# Sheet2.net
KiCad netlist of a schematic drawn in Altium Designer
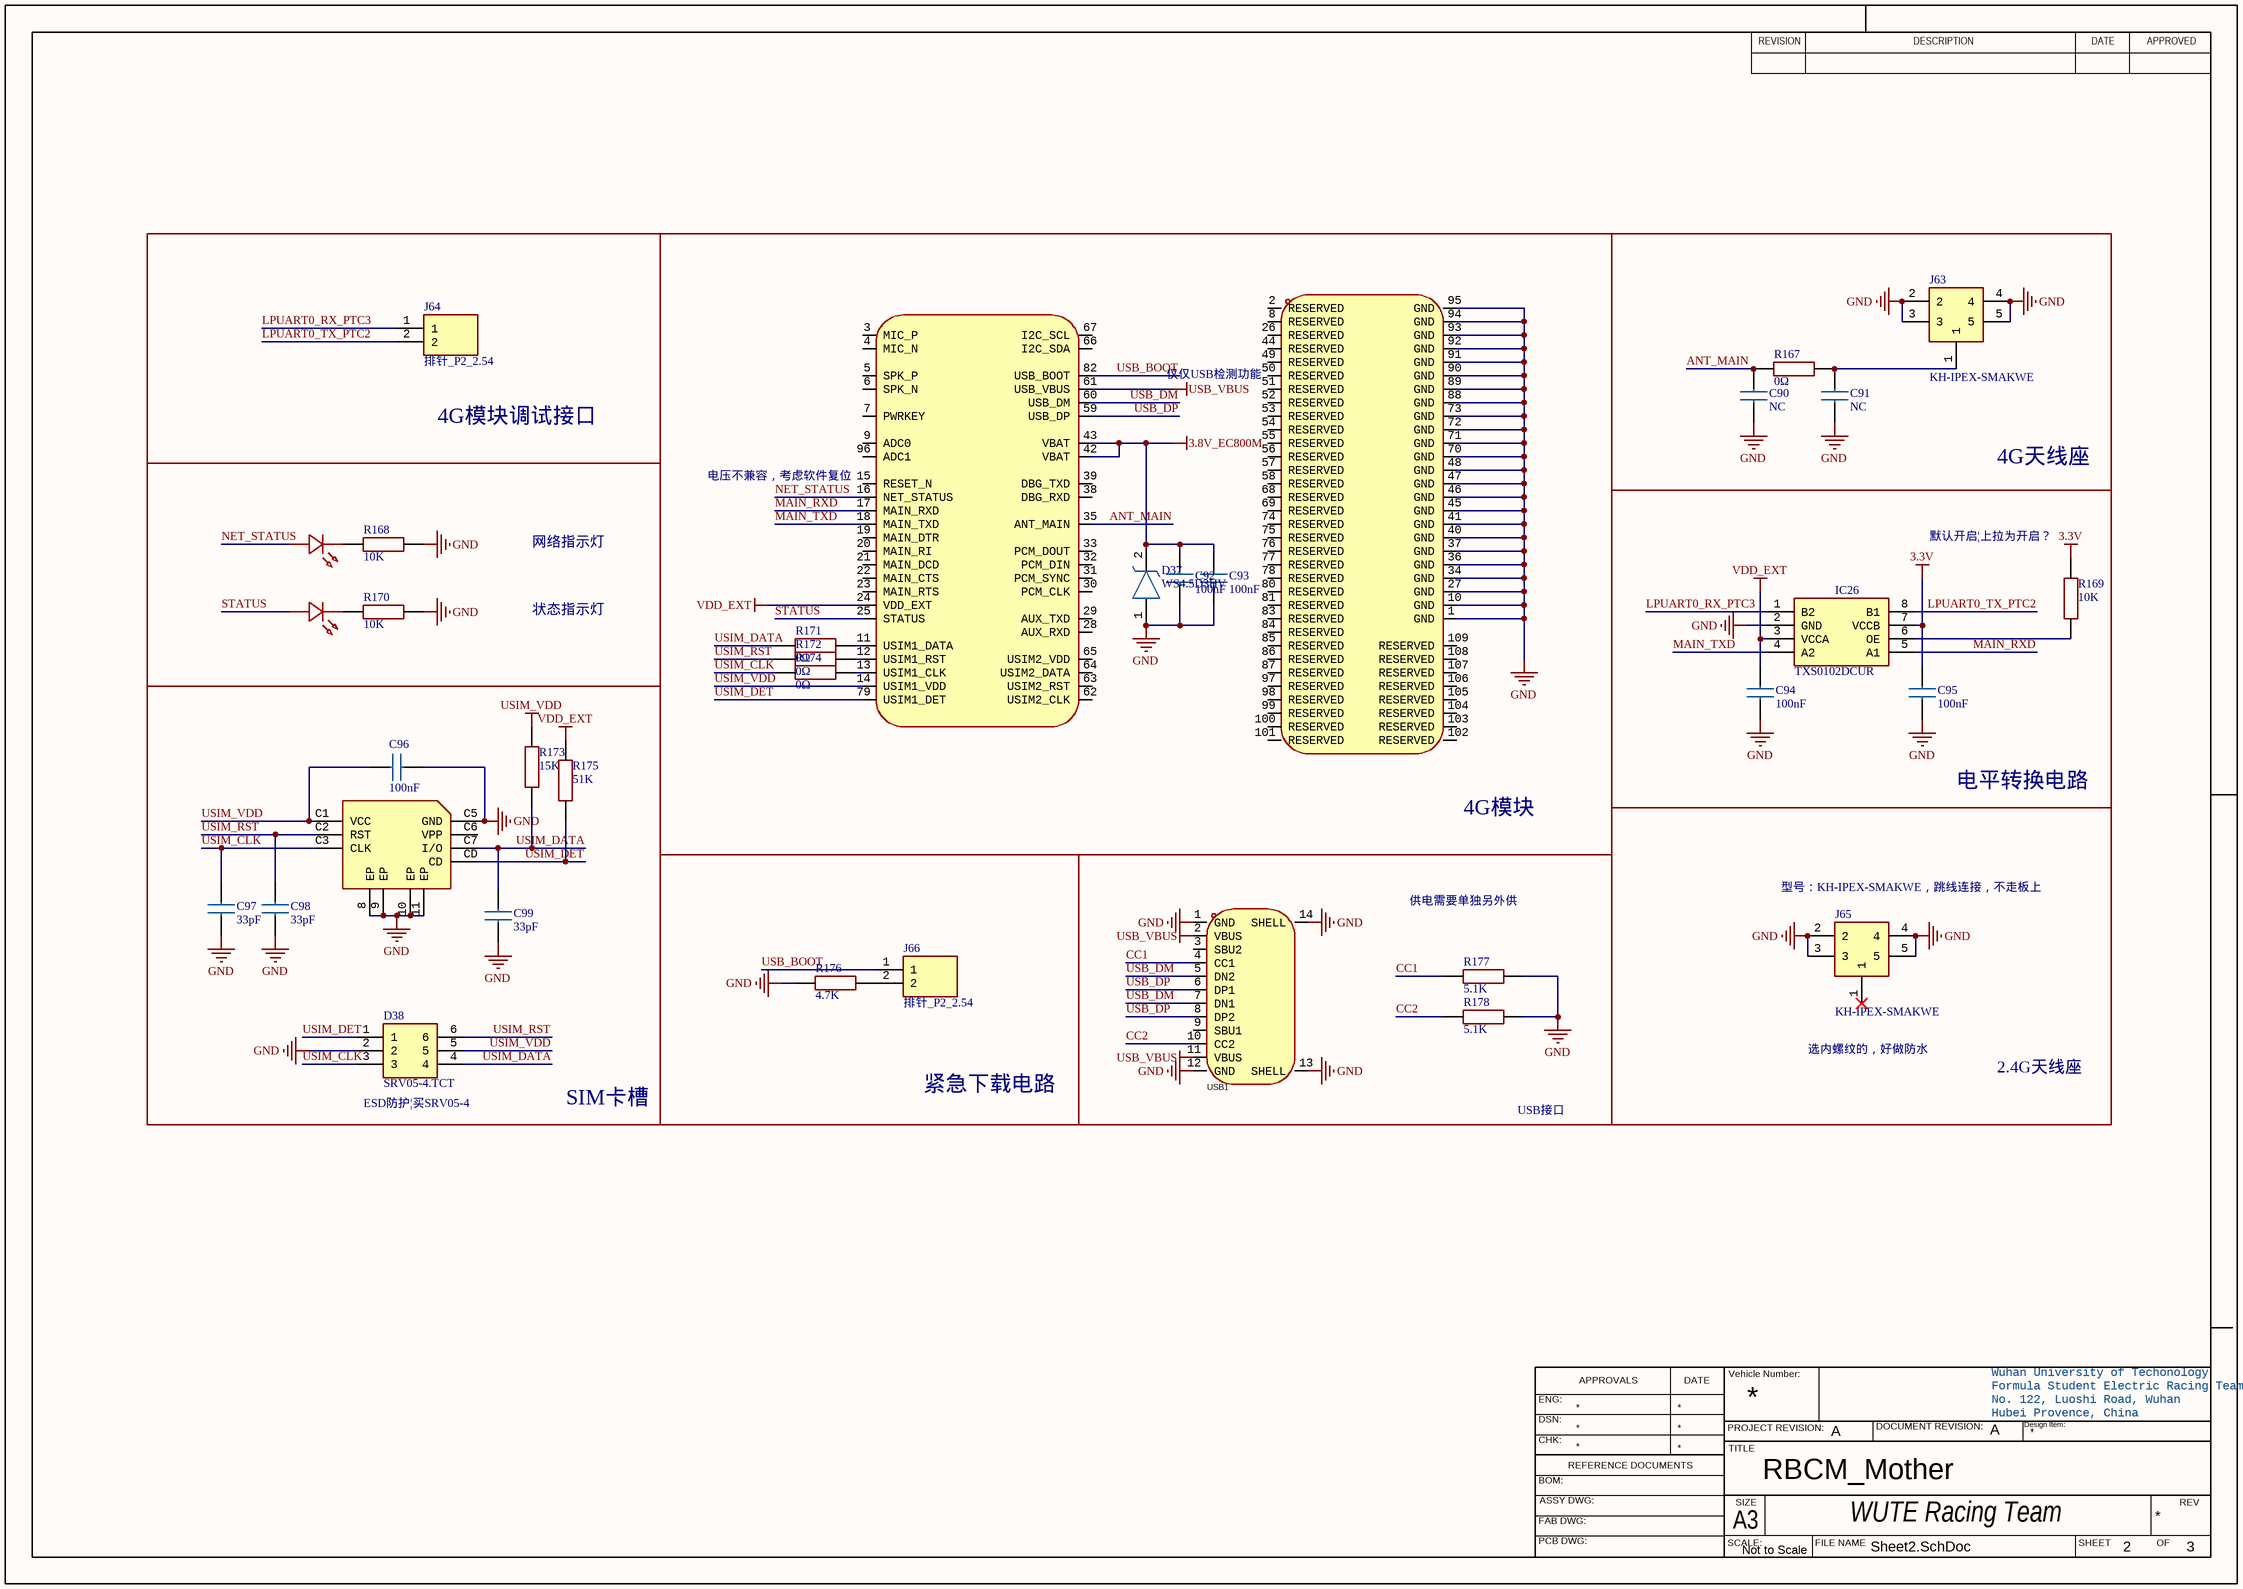
[diagram p0: Sheet2.SchDoc]

(export (version "E")
  (design (tool "Eeschema 10.0.6"))
  (components
    (comp (ref "C90")
      (value "NC")
      (footprint "CAPC1608X90N")
      (description "Capacitor")
      (fields
        (field (name "MANUFACTURER_PART_NUMBER") "CC0603KRX7R9BB104")
        (field (name "MOUSER PART NUMBER") "603-CC603KRX7R9BB104")
      )
      (libsource (lib "Resistor^Capacitor^Inductor") (part "C0603"))
    )
    (comp (ref "C91")
      (value "NC")
      (footprint "CAPC1608X90N")
      (description "Capacitor")
      (fields
        (field (name "MANUFACTURER_PART_NUMBER") "CC0603KRX7R9BB104")
        (field (name "MOUSER PART NUMBER") "603-CC603KRX7R9BB104")
      )
      (libsource (lib "Resistor^Capacitor^Inductor") (part "C0603"))
    )
    (comp (ref "C92")
      (value "100nF")
      (footprint "CAPC1608X90N")
      (description "Capacitor")
      (fields
        (field (name "MANUFACTURER_PART_NUMBER") "CC0603KRX7R9BB104")
        (field (name "MOUSER PART NUMBER") "603-CC603KRX7R9BB104")
      )
      (libsource (lib "Resistor^Capacitor^Inductor") (part "C0603"))
    )
    (comp (ref "C93")
      (value "100nF")
      (footprint "CAPC1608X90N")
      (description "Capacitor")
      (fields
        (field (name "MANUFACTURER_PART_NUMBER") "CC0603KRX7R9BB104")
        (field (name "MOUSER PART NUMBER") "603-CC603KRX7R9BB104")
      )
      (libsource (lib "Resistor^Capacitor^Inductor") (part "C0603"))
    )
    (comp (ref "C94")
      (value "100nF")
      (footprint "CAPC1608X90N")
      (description "Capacitor CC0603KRX7R9BB104")
      (fields
        (field (name "MANUFACTURER_PART_NUMBER") "CC0603KRX7R9BB104")
        (field (name "MOUSER PART NUMBER") "603-CC603KRX7R9BB104")
      )
      (libsource (lib "") (part "C0603_1"))
    )
    (comp (ref "C95")
      (value "100nF")
      (footprint "CAPC1608X90N")
      (description "Capacitor CC0603KRX7R9BB104")
      (fields
        (field (name "MANUFACTURER_PART_NUMBER") "CC0603KRX7R9BB104")
        (field (name "MOUSER PART NUMBER") "603-CC603KRX7R9BB104")
      )
      (libsource (lib "") (part "C0603_1"))
    )
    (comp (ref "C96")
      (value "100nF")
      (footprint "CAPC1608X90N")
      (description "Capacitor")
      (fields
        (field (name "MANUFACTURER_PART_NUMBER") "CC0603KRX7R9BB104")
        (field (name "MOUSER PART NUMBER") "603-CC603KRX7R9BB104")
      )
      (libsource (lib "Resistor^Capacitor^Inductor") (part "C0603"))
    )
    (comp (ref "C97")
      (value "33pF")
      (footprint "CAPC1608X90N")
      (description "Capacitor")
      (fields
        (field (name "MANUFACTURER_PART_NUMBER") "CC0603KRX7R9BB104")
        (field (name "MOUSER PART NUMBER") "603-CC603KRX7R9BB104")
      )
      (libsource (lib "Resistor^Capacitor^Inductor") (part "C0603"))
    )
    (comp (ref "C98")
      (value "33pF")
      (footprint "CAPC1608X90N")
      (description "Capacitor")
      (fields
        (field (name "MANUFACTURER_PART_NUMBER") "CC0603KRX7R9BB104")
        (field (name "MOUSER PART NUMBER") "603-CC603KRX7R9BB104")
      )
      (libsource (lib "Resistor^Capacitor^Inductor") (part "C0603"))
    )
    (comp (ref "C99")
      (value "33pF")
      (footprint "CAPC1608X90N")
      (description "Capacitor")
      (fields
        (field (name "MANUFACTURER_PART_NUMBER") "CC0603KRX7R9BB104")
        (field (name "MOUSER PART NUMBER") "603-CC603KRX7R9BB104")
      )
      (libsource (lib "Resistor^Capacitor^Inductor") (part "C0603"))
    )
    (comp (ref "CARD1")
      (value "SMN-303")
      (footprint "SIM-SMD_SMN-303")
      (fields (field (name "MANUFACTURER") "XUNPU(讯普)"))
      (libsource (lib "Connector") (part "SMN-303"))
    )
    (comp (ref "D37")
      (value "WS4.5D3HV")
      (footprint "WS45D3HV")
      (description "TVS Diode (Uni-directional)")
      (libsource (lib "Diodes") (part "WS4.5D3HV"))
    )
    (comp (ref "D38")
      (value "SRV05-4.TCT")
      (footprint "SOT95P280X145-6N")
      (description "TVS Diode (Uni-directional)")
      (fields (field (name "MOUSER PART NUMBER") "947-SRV05-4.TCT"))
      (libsource (lib "Diodes") (part "SRV05-4.TCT"))
    )
    (comp (ref "IC26")
      (value "TXS0102DCUR")
      (footprint "SOP50P310X90-8N")
      (description "Integrated Circuit")
      (fields (field (name "MOUSER PART NUMBER") "595-TXS0102DCUR"))
      (libsource (lib "Switch^Relay") (part "TXS0102DCUR"))
    )
    (comp (ref "J63")
      (value "KH-IPEX-SMAKWE")
      (footprint "KHIPEXSMAKWE")
      (description "Connector")
      (libsource (lib "Connector") (part "KH-IPEX-SMAKWE"))
    )
    (comp (ref "J64")
      (value "排针_P2_2.54")
      (footprint "HDRV2W66P0X254_1X2_508X250X880P")
      (description "Connector")
      (fields (field (name "MANUFACTURER_PART_NUMBER") "B-2100S02P-A110"))
      (libsource (lib "Connector") (part "排针_P2_2.54"))
    )
    (comp (ref "J65")
      (value "KH-IPEX-SMAKWE")
      (footprint "KHIPEXSMAKWE")
      (description "Connector")
      (libsource (lib "Connector") (part "KH-IPEX-SMAKWE"))
    )
    (comp (ref "J66")
      (value "排针_P2_2.54")
      (footprint "HDRV2W66P0X254_1X2_508X250X880P")
      (description "Connector")
      (fields (field (name "MANUFACTURER_PART_NUMBER") "B-2100S02P-A110"))
      (libsource (lib "Connector") (part "排针_P2_2.54"))
    )
    (comp (ref "LED3")
      (value "XL-1606UGC")
      (footprint "LED-SMD_L1.7-W1.1-R-RD_GREEN")
      (fields (field (name "MANUFACTURER") "XINGLIGHT(成兴光)"))
      (libsource (lib "Diodes") (part "XL-1606UGC"))
    )
    (comp (ref "LED4")
      (value "XL-1606UGC")
      (footprint "LED-SMD_L1.7-W1.1-R-RD_GREEN")
      (fields (field (name "MANUFACTURER") "XINGLIGHT(成兴光)"))
      (libsource (lib "Diodes") (part "XL-1606UGC"))
    )
    (comp (ref "R167")
      (value "0Ω")
      (footprint "RESC1608X55N")
      (description "Resistor")
      (fields (field (name "MANUFACTURER_PART_NUMBER") "0603WAF1002T5E"))
      (libsource (lib "") (part "R0603_1"))
    )
    (comp (ref "R168")
      (value "10K")
      (footprint "RESC1608X55N")
      (description "Resistor")
      (fields (field (name "MANUFACTURER_PART_NUMBER") "0603WAF1002T5E"))
      (libsource (lib "Resistor^Capacitor^Inductor") (part "R0603"))
    )
    (comp (ref "R169")
      (value "10K")
      (footprint "RESC1608X55N")
      (description "Resistor 0603WAF1002T5E")
      (fields (field (name "MANUFACTURER_PART_NUMBER") "0603WAF1002T5E"))
      (libsource (lib "") (part "R0603_2"))
    )
    (comp (ref "R170")
      (value "10K")
      (footprint "RESC1608X55N")
      (description "Resistor")
      (fields (field (name "MANUFACTURER_PART_NUMBER") "0603WAF1002T5E"))
      (libsource (lib "Resistor^Capacitor^Inductor") (part "R0603"))
    )
    (comp (ref "R171")
      (value "0Ω")
      (footprint "RESC1608X55N")
      (description "Resistor")
      (fields (field (name "MANUFACTURER_PART_NUMBER") "0603WAF1002T5E"))
      (libsource (lib "") (part "R0603_1"))
    )
    (comp (ref "R172")
      (value "0Ω")
      (footprint "RESC1608X55N")
      (description "Resistor")
      (fields (field (name "MANUFACTURER_PART_NUMBER") "0603WAF1002T5E"))
      (libsource (lib "") (part "R0603_1"))
    )
    (comp (ref "R173")
      (value "15K")
      (footprint "RESC1608X55N")
      (description "Resistor")
      (fields (field (name "MANUFACTURER_PART_NUMBER") "0603WAF1002T5E"))
      (libsource (lib "") (part "R0603_4"))
    )
    (comp (ref "R174")
      (value "0Ω")
      (footprint "RESC1608X55N")
      (description "Resistor")
      (fields (field (name "MANUFACTURER_PART_NUMBER") "0603WAF1002T5E"))
      (libsource (lib "") (part "R0603_1"))
    )
    (comp (ref "R175")
      (value "51K")
      (footprint "RESC1608X55N")
      (description "Resistor")
      (fields (field (name "MANUFACTURER_PART_NUMBER") "0603WAF1002T5E"))
      (libsource (lib "") (part "R0603_4"))
    )
    (comp (ref "R176")
      (value "4.7K")
      (footprint "RESC1608X55N")
      (description "Resistor")
      (fields (field (name "MANUFACTURER_PART_NUMBER") "0603WAF1002T5E"))
      (libsource (lib "") (part "R0603_1"))
    )
    (comp (ref "R177")
      (value "5.1K")
      (footprint "RESC1608X55N")
      (description "Resistor 0603WAF1002T5E")
      (fields (field (name "MANUFACTURER_PART_NUMBER") "0603WAF1002T5E"))
      (libsource (lib "") (part "R0603_3"))
    )
    (comp (ref "R178")
      (value "5.1K")
      (footprint "RESC1608X55N")
      (description "Resistor 0603WAF1002T5E")
      (fields (field (name "MANUFACTURER_PART_NUMBER") "0603WAF1002T5E"))
      (libsource (lib "") (part "R0603_3"))
    )
    (comp (ref "U2")
      (value "EC800MCNGA-I05-SGNSA")
      (footprint "LCC-109_L17.7-W15.8-P1.10_EC800M-CN")
      (fields (field (name "MANUFACTURER") "Quectel(移远)"))
      (libsource (lib "MCU^MPU") (part "EC800MCNGA-I05-SGNSA"))
    )
    (comp (ref "USB1")
      (value "TYPE-C 16PIN 2MD(073)")
      (footprint "USB-C-SMD_TYPE-C-6PIN-2MD-073")
      (fields (field (name "MANUFACTURER") "SHOU HAN(首韩)"))
      (libsource (lib "Connector") (part "TYPE-C 16PIN 2MD(073)"))
    )
  )
  (nets
    (net (code "1") (name "/ANT_MAIN") (class "Default")
      (node (ref "C90") (pin "2") (pinfunction "2_2") (pintype "passive"))
      (node (ref "R167") (pin "1") (pinfunction "1_1") (pintype "passive"))
      (node (ref "U2") (pin "35") (pinfunction "ANT_MAIN_35") (pintype "passive"))
    )
    (net (code "2") (name "/CC1") (class "Default")
      (node (ref "R177") (pin "1") (pinfunction "1_1") (pintype "passive"))
      (node (ref "USB1") (pin "4") (pinfunction "CC1_4") (pintype "passive"))
    )
    (net (code "3") (name "/CC2") (class "Default")
      (node (ref "R178") (pin "1") (pinfunction "1_1") (pintype "passive"))
      (node (ref "USB1") (pin "10") (pinfunction "CC2_10") (pintype "passive"))
    )
    (net (code "4") (name "/LPUART0_RX_PTC3") (class "Default")
      (node (ref "IC26") (pin "1") (pinfunction "B2_1") (pintype "passive"))
      (node (ref "J64") (pin "1") (pinfunction "1_1") (pintype "passive"))
    )
    (net (code "5") (name "/LPUART0_TX_PTC2") (class "Default")
      (node (ref "IC26") (pin "8") (pinfunction "B1_8") (pintype "passive"))
      (node (ref "J64") (pin "2") (pinfunction "2_2") (pintype "passive"))
    )
    (net (code "6") (name "/MAIN_RXD") (class "Default")
      (node (ref "IC26") (pin "5") (pinfunction "A1_5") (pintype "passive"))
      (node (ref "U2") (pin "17") (pinfunction "MAIN_RXD_17") (pintype "passive"))
    )
    (net (code "7") (name "/MAIN_TXD") (class "Default")
      (node (ref "IC26") (pin "4") (pinfunction "A2_4") (pintype "passive"))
      (node (ref "U2") (pin "18") (pinfunction "MAIN_TXD_18") (pintype "passive"))
    )
    (net (code "8") (name "/NET_STATUS") (class "Default")
      (node (ref "LED3") (pin "1") (pinfunction "A_1") (pintype "passive"))
      (node (ref "U2") (pin "16") (pinfunction "NET_STATUS_16") (pintype "passive"))
    )
    (net (code "9") (name "/STATUS") (class "Default")
      (node (ref "LED4") (pin "1") (pinfunction "A_1") (pintype "passive"))
      (node (ref "U2") (pin "25") (pinfunction "STATUS_25") (pintype "passive"))
    )
    (net (code "10") (name "/USB_BOOT") (class "Default")
      (node (ref "J66") (pin "1") (pinfunction "1_1") (pintype "passive"))
      (node (ref "U2") (pin "82") (pinfunction "USB_BOOT_82") (pintype "passive"))
    )
    (net (code "11") (name "/USB_DM") (class "Default")
      (node (ref "U2") (pin "60") (pinfunction "USB_DM_60") (pintype "passive"))
      (node (ref "USB1") (pin "5") (pinfunction "DN2_5") (pintype "passive"))
      (node (ref "USB1") (pin "7") (pinfunction "DN1_7") (pintype "passive"))
    )
    (net (code "12") (name "/USB_DP") (class "Default")
      (node (ref "U2") (pin "59") (pinfunction "USB_DP_59") (pintype "passive"))
      (node (ref "USB1") (pin "6") (pinfunction "DP1_6") (pintype "passive"))
      (node (ref "USB1") (pin "8") (pinfunction "DP2_8") (pintype "passive"))
    )
    (net (code "13") (name "/USIM_CLK") (class "Default")
      (node (ref "C97") (pin "1") (pinfunction "1_1") (pintype "passive"))
      (node (ref "CARD1") (pin "C3") (pinfunction "CLK_C3") (pintype "passive"))
      (node (ref "D38") (pin "3") (pinfunction "3_3") (pintype "passive"))
      (node (ref "R174") (pin "1") (pinfunction "1_1") (pintype "passive"))
    )
    (net (code "14") (name "/USIM_DATA") (class "Default")
      (node (ref "C99") (pin "1") (pinfunction "1_1") (pintype "passive"))
      (node (ref "CARD1") (pin "C7") (pinfunction "I/O_C7") (pintype "passive"))
      (node (ref "D38") (pin "4") (pinfunction "4_4") (pintype "passive"))
      (node (ref "R171") (pin "1") (pinfunction "1_1") (pintype "passive"))
      (node (ref "R173") (pin "1") (pinfunction "1_1") (pintype "passive"))
    )
    (net (code "15") (name "/USIM_DET") (class "Default")
      (node (ref "CARD1") (pin "CD") (pinfunction "CD_CD") (pintype "passive"))
      (node (ref "D38") (pin "1") (pinfunction "1_1") (pintype "passive"))
      (node (ref "R175") (pin "1") (pinfunction "1_1") (pintype "passive"))
      (node (ref "U2") (pin "79") (pinfunction "USIM1_DET_79") (pintype "passive"))
    )
    (net (code "16") (name "/USIM_RST") (class "Default")
      (node (ref "C98") (pin "1") (pinfunction "1_1") (pintype "passive"))
      (node (ref "CARD1") (pin "C2") (pinfunction "RST_C2") (pintype "passive"))
      (node (ref "D38") (pin "6") (pinfunction "6_6") (pintype "passive"))
      (node (ref "R172") (pin "1") (pinfunction "1_1") (pintype "passive"))
    )
    (net (code "17") (name "3.3V") (class "Default")
      (node (ref "C95") (pin "1") (pinfunction "1_1") (pintype "passive"))
      (node (ref "IC26") (pin "7") (pinfunction "VCCB_7") (pintype "passive"))
      (node (ref "R169") (pin "1") (pinfunction "1_1") (pintype "passive"))
    )
    (net (code "18") (name "3.8V_EC800M") (class "Default")
      (node (ref "C92") (pin "2") (pinfunction "2_2") (pintype "passive"))
      (node (ref "C93") (pin "2") (pinfunction "2_2") (pintype "passive"))
      (node (ref "D37") (pin "2") (pinfunction "K_2") (pintype "passive"))
      (node (ref "U2") (pin "42") (pinfunction "VBAT_42") (pintype "passive"))
      (node (ref "U2") (pin "43") (pinfunction "VBAT_43") (pintype "passive"))
    )
    (net (code "19") (name "GND") (class "Default")
      (node (ref "C90") (pin "1") (pinfunction "1_1") (pintype "passive"))
      (node (ref "C91") (pin "1") (pinfunction "1_1") (pintype "passive"))
      (node (ref "C92") (pin "1") (pinfunction "1_1") (pintype "passive"))
      (node (ref "C93") (pin "1") (pinfunction "1_1") (pintype "passive"))
      (node (ref "C94") (pin "2") (pinfunction "2_2") (pintype "passive"))
      (node (ref "C95") (pin "2") (pinfunction "2_2") (pintype "passive"))
      (node (ref "C96") (pin "1") (pinfunction "1_1") (pintype "passive"))
      (node (ref "C97") (pin "2") (pinfunction "2_2") (pintype "passive"))
      (node (ref "C98") (pin "2") (pinfunction "2_2") (pintype "passive"))
      (node (ref "C99") (pin "2") (pinfunction "2_2") (pintype "passive"))
      (node (ref "CARD1") (pin "10") (pinfunction "EP_10") (pintype "passive"))
      (node (ref "CARD1") (pin "11") (pinfunction "EP_11") (pintype "passive"))
      (node (ref "CARD1") (pin "8") (pinfunction "EP_8") (pintype "passive"))
      (node (ref "CARD1") (pin "9") (pinfunction "EP_9") (pintype "passive"))
      (node (ref "CARD1") (pin "C5") (pinfunction "GND_C5") (pintype "passive"))
      (node (ref "D37") (pin "1") (pinfunction "A_1") (pintype "passive"))
      (node (ref "D38") (pin "2") (pinfunction "2_2") (pintype "passive"))
      (node (ref "IC26") (pin "2") (pinfunction "GND_2") (pintype "passive"))
      (node (ref "J63") (pin "2") (pinfunction "2_2") (pintype "passive"))
      (node (ref "J63") (pin "3") (pinfunction "3_3") (pintype "passive"))
      (node (ref "J63") (pin "4") (pinfunction "4_4") (pintype "passive"))
      (node (ref "J63") (pin "5") (pinfunction "5_5") (pintype "passive"))
      (node (ref "J65") (pin "2") (pinfunction "2_2") (pintype "passive"))
      (node (ref "J65") (pin "3") (pinfunction "3_3") (pintype "passive"))
      (node (ref "J65") (pin "4") (pinfunction "4_4") (pintype "passive"))
      (node (ref "J65") (pin "5") (pinfunction "5_5") (pintype "passive"))
      (node (ref "R168") (pin "1") (pinfunction "1_1") (pintype "passive"))
      (node (ref "R170") (pin "1") (pinfunction "1_1") (pintype "passive"))
      (node (ref "R176") (pin "1") (pinfunction "1_1") (pintype "passive"))
      (node (ref "R177") (pin "2") (pinfunction "2_2") (pintype "passive"))
      (node (ref "R178") (pin "2") (pinfunction "2_2") (pintype "passive"))
      (node (ref "U2") (pin "1") (pinfunction "GND_1") (pintype "passive"))
      (node (ref "U2") (pin "10") (pinfunction "GND_10") (pintype "passive"))
      (node (ref "U2") (pin "27") (pinfunction "GND_27") (pintype "passive"))
      (node (ref "U2") (pin "34") (pinfunction "GND_34") (pintype "passive"))
      (node (ref "U2") (pin "36") (pinfunction "GND_36") (pintype "passive"))
      (node (ref "U2") (pin "37") (pinfunction "GND_37") (pintype "passive"))
      (node (ref "U2") (pin "40") (pinfunction "GND_40") (pintype "passive"))
      (node (ref "U2") (pin "41") (pinfunction "GND_41") (pintype "passive"))
      (node (ref "U2") (pin "45") (pinfunction "GND_45") (pintype "passive"))
      (node (ref "U2") (pin "46") (pinfunction "GND_46") (pintype "passive"))
      (node (ref "U2") (pin "47") (pinfunction "GND_47") (pintype "passive"))
      (node (ref "U2") (pin "48") (pinfunction "GND_48") (pintype "passive"))
      (node (ref "U2") (pin "70") (pinfunction "GND_70") (pintype "passive"))
      (node (ref "U2") (pin "71") (pinfunction "GND_71") (pintype "passive"))
      (node (ref "U2") (pin "72") (pinfunction "GND_72") (pintype "passive"))
      (node (ref "U2") (pin "73") (pinfunction "GND_73") (pintype "passive"))
      (node (ref "U2") (pin "88") (pinfunction "GND_88") (pintype "passive"))
      (node (ref "U2") (pin "89") (pinfunction "GND_89") (pintype "passive"))
      (node (ref "U2") (pin "90") (pinfunction "GND_90") (pintype "passive"))
      (node (ref "U2") (pin "91") (pinfunction "GND_91") (pintype "passive"))
      (node (ref "U2") (pin "92") (pinfunction "GND_92") (pintype "passive"))
      (node (ref "U2") (pin "93") (pinfunction "GND_93") (pintype "passive"))
      (node (ref "U2") (pin "94") (pinfunction "GND_94") (pintype "passive"))
      (node (ref "U2") (pin "95") (pinfunction "GND_95") (pintype "passive"))
      (node (ref "USB1") (pin "1") (pinfunction "GND_1") (pintype "passive"))
      (node (ref "USB1") (pin "12") (pinfunction "GND_12") (pintype "passive"))
      (node (ref "USB1") (pin "13") (pinfunction "SHELL_13") (pintype "passive"))
      (node (ref "USB1") (pin "14") (pinfunction "SHELL_14") (pintype "passive"))
    )
    (net (code "20") (name "Net-(C91-Pad2)") (class "Default")
      (node (ref "C91") (pin "2") (pinfunction "2_2") (pintype "passive"))
      (node (ref "J63") (pin "1") (pinfunction "1_1") (pintype "passive"))
      (node (ref "R167") (pin "2") (pinfunction "2_2") (pintype "passive"))
    )
    (net (code "21") (name "Net-(IC26-OE)") (class "Default")
      (node (ref "IC26") (pin "6") (pinfunction "OE_6") (pintype "passive"))
      (node (ref "R169") (pin "2") (pinfunction "2_2") (pintype "passive"))
    )
    (net (code "22") (name "Net-(J66-Pad2)") (class "Default")
      (node (ref "J66") (pin "2") (pinfunction "2_2") (pintype "passive"))
      (node (ref "R176") (pin "2") (pinfunction "2_2") (pintype "passive"))
    )
    (net (code "23") (name "Net-(LED3-K)") (class "Default")
      (node (ref "LED3") (pin "2") (pinfunction "K_2") (pintype "passive"))
      (node (ref "R168") (pin "2") (pinfunction "2_2") (pintype "passive"))
    )
    (net (code "24") (name "Net-(LED4-K)") (class "Default")
      (node (ref "LED4") (pin "2") (pinfunction "K_2") (pintype "passive"))
      (node (ref "R170") (pin "2") (pinfunction "2_2") (pintype "passive"))
    )
    (net (code "25") (name "Net-(U2A-USIM1_CLK)") (class "Default")
      (node (ref "R174") (pin "2") (pinfunction "2_2") (pintype "passive"))
      (node (ref "U2") (pin "13") (pinfunction "USIM1_CLK_13") (pintype "passive"))
    )
    (net (code "26") (name "Net-(U2A-USIM1_DATA)") (class "Default")
      (node (ref "R171") (pin "2") (pinfunction "2_2") (pintype "passive"))
      (node (ref "U2") (pin "11") (pinfunction "USIM1_DATA_11") (pintype "passive"))
    )
    (net (code "27") (name "Net-(U2A-USIM1_RST)") (class "Default")
      (node (ref "R172") (pin "2") (pinfunction "2_2") (pintype "passive"))
      (node (ref "U2") (pin "12") (pinfunction "USIM1_RST_12") (pintype "passive"))
    )
    (net (code "28") (name "USB_VBUS") (class "Default")
      (node (ref "U2") (pin "61") (pinfunction "USB_VBUS_61") (pintype "passive"))
      (node (ref "USB1") (pin "11") (pinfunction "VBUS_11") (pintype "passive"))
      (node (ref "USB1") (pin "2") (pinfunction "VBUS_2") (pintype "passive"))
    )
    (net (code "29") (name "USIM_VDD") (class "Default")
      (node (ref "C96") (pin "2") (pinfunction "2_2") (pintype "passive"))
      (node (ref "CARD1") (pin "C1") (pinfunction "VCC_C1") (pintype "passive"))
      (node (ref "D38") (pin "5") (pinfunction "5_5") (pintype "passive"))
      (node (ref "R173") (pin "2") (pinfunction "2_2") (pintype "passive"))
      (node (ref "U2") (pin "14") (pinfunction "USIM1_VDD_14") (pintype "passive"))
    )
    (net (code "30") (name "VDD_EXT") (class "Default")
      (node (ref "C94") (pin "1") (pinfunction "1_1") (pintype "passive"))
      (node (ref "IC26") (pin "3") (pinfunction "VCCA_3") (pintype "passive"))
      (node (ref "R175") (pin "2") (pinfunction "2_2") (pintype "passive"))
      (node (ref "U2") (pin "24") (pinfunction "VDD_EXT_24") (pintype "passive"))
    )
    (net (code "31") (name "unconnected-(CARD1-VPP-PadC6)") (class "Default")
      (node (ref "CARD1") (pin "C6") (pinfunction "VPP_C6") (pintype "passive"))
    )
    (net (code "32") (name "unconnected-(J65-Pad1)") (class "Default")
      (node (ref "J65") (pin "1") (pinfunction "1_1") (pintype "passive+no_connect"))
    )
    (net (code "33") (name "unconnected-(U2A-ADC0-Pad9)") (class "Default")
      (node (ref "U2") (pin "9") (pinfunction "ADC0_9") (pintype "passive"))
    )
    (net (code "34") (name "unconnected-(U2A-ADC1-Pad96)") (class "Default")
      (node (ref "U2") (pin "96") (pinfunction "ADC1_96") (pintype "passive"))
    )
    (net (code "35") (name "unconnected-(U2A-AUX_RXD-Pad28)") (class "Default")
      (node (ref "U2") (pin "28") (pinfunction "AUX_RXD_28") (pintype "passive"))
    )
    (net (code "36") (name "unconnected-(U2A-AUX_TXD-Pad29)") (class "Default")
      (node (ref "U2") (pin "29") (pinfunction "AUX_TXD_29") (pintype "passive"))
    )
    (net (code "37") (name "unconnected-(U2A-DBG_RXD-Pad38)") (class "Default")
      (node (ref "U2") (pin "38") (pinfunction "DBG_RXD_38") (pintype "passive"))
    )
    (net (code "38") (name "unconnected-(U2A-DBG_TXD-Pad39)") (class "Default")
      (node (ref "U2") (pin "39") (pinfunction "DBG_TXD_39") (pintype "passive"))
    )
    (net (code "39") (name "unconnected-(U2A-I2C_SCL-Pad67)") (class "Default")
      (node (ref "U2") (pin "67") (pinfunction "I2C_SCL_67") (pintype "passive"))
    )
    (net (code "40") (name "unconnected-(U2A-I2C_SDA-Pad66)") (class "Default")
      (node (ref "U2") (pin "66") (pinfunction "I2C_SDA_66") (pintype "passive"))
    )
    (net (code "41") (name "unconnected-(U2A-MAIN_CTS-Pad22)") (class "Default")
      (node (ref "U2") (pin "22") (pinfunction "MAIN_CTS_22") (pintype "passive"))
    )
    (net (code "42") (name "unconnected-(U2A-MAIN_DCD-Pad21)") (class "Default")
      (node (ref "U2") (pin "21") (pinfunction "MAIN_DCD_21") (pintype "passive"))
    )
    (net (code "43") (name "unconnected-(U2A-MAIN_DTR-Pad19)") (class "Default")
      (node (ref "U2") (pin "19") (pinfunction "MAIN_DTR_19") (pintype "passive"))
    )
    (net (code "44") (name "unconnected-(U2A-MAIN_RI-Pad20)") (class "Default")
      (node (ref "U2") (pin "20") (pinfunction "MAIN_RI_20") (pintype "passive"))
    )
    (net (code "45") (name "unconnected-(U2A-MAIN_RTS-Pad23)") (class "Default")
      (node (ref "U2") (pin "23") (pinfunction "MAIN_RTS_23") (pintype "passive"))
    )
    (net (code "46") (name "unconnected-(U2A-MIC_N-Pad4)") (class "Default")
      (node (ref "U2") (pin "4") (pinfunction "MIC_N_4") (pintype "passive"))
    )
    (net (code "47") (name "unconnected-(U2A-MIC_P-Pad3)") (class "Default")
      (node (ref "U2") (pin "3") (pinfunction "MIC_P_3") (pintype "passive"))
    )
    (net (code "48") (name "unconnected-(U2A-PCM_CLK-Pad30)") (class "Default")
      (node (ref "U2") (pin "30") (pinfunction "PCM_CLK_30") (pintype "passive"))
    )
    (net (code "49") (name "unconnected-(U2A-PCM_DIN-Pad32)") (class "Default")
      (node (ref "U2") (pin "32") (pinfunction "PCM_DIN_32") (pintype "passive"))
    )
    (net (code "50") (name "unconnected-(U2A-PCM_DOUT-Pad33)") (class "Default")
      (node (ref "U2") (pin "33") (pinfunction "PCM_DOUT_33") (pintype "passive"))
    )
    (net (code "51") (name "unconnected-(U2A-PCM_SYNC-Pad31)") (class "Default")
      (node (ref "U2") (pin "31") (pinfunction "PCM_SYNC_31") (pintype "passive"))
    )
    (net (code "52") (name "unconnected-(U2A-PWRKEY-Pad7)") (class "Default")
      (node (ref "U2") (pin "7") (pinfunction "PWRKEY_7") (pintype "passive"))
    )
    (net (code "53") (name "unconnected-(U2A-RESET_N-Pad15)") (class "Default")
      (node (ref "U2") (pin "15") (pinfunction "RESET_N_15") (pintype "passive"))
    )
    (net (code "54") (name "unconnected-(U2A-SPK_N-Pad6)") (class "Default")
      (node (ref "U2") (pin "6") (pinfunction "SPK_N_6") (pintype "passive"))
    )
    (net (code "55") (name "unconnected-(U2A-SPK_P-Pad5)") (class "Default")
      (node (ref "U2") (pin "5") (pinfunction "SPK_P_5") (pintype "passive"))
    )
    (net (code "56") (name "unconnected-(U2A-USIM2_CLK-Pad62)") (class "Default")
      (node (ref "U2") (pin "62") (pinfunction "USIM2_CLK_62") (pintype "passive"))
    )
    (net (code "57") (name "unconnected-(U2A-USIM2_DATA-Pad64)") (class "Default")
      (node (ref "U2") (pin "64") (pinfunction "USIM2_DATA_64") (pintype "passive"))
    )
    (net (code "58") (name "unconnected-(U2A-USIM2_RST-Pad63)") (class "Default")
      (node (ref "U2") (pin "63") (pinfunction "USIM2_RST_63") (pintype "passive"))
    )
    (net (code "59") (name "unconnected-(U2A-USIM2_VDD-Pad65)") (class "Default")
      (node (ref "U2") (pin "65") (pinfunction "USIM2_VDD_65") (pintype "passive"))
    )
    (net (code "60") (name "unconnected-(U2B-RESERVED-Pad2)") (class "Default")
      (node (ref "U2") (pin "2") (pinfunction "RESERVED_2") (pintype "passive"))
    )
    (net (code "61") (name "unconnected-(U2B-RESERVED-Pad8)") (class "Default")
      (node (ref "U2") (pin "8") (pinfunction "RESERVED_8") (pintype "passive"))
    )
    (net (code "62") (name "unconnected-(U2B-RESERVED-Pad26)") (class "Default")
      (node (ref "U2") (pin "26") (pinfunction "RESERVED_26") (pintype "passive"))
    )
    (net (code "63") (name "unconnected-(U2B-RESERVED-Pad44)") (class "Default")
      (node (ref "U2") (pin "44") (pinfunction "RESERVED_44") (pintype "passive"))
    )
    (net (code "64") (name "unconnected-(U2B-RESERVED-Pad49)") (class "Default")
      (node (ref "U2") (pin "49") (pinfunction "RESERVED_49") (pintype "passive"))
    )
    (net (code "65") (name "unconnected-(U2B-RESERVED-Pad50)") (class "Default")
      (node (ref "U2") (pin "50") (pinfunction "RESERVED_50") (pintype "passive"))
    )
    (net (code "66") (name "unconnected-(U2B-RESERVED-Pad51)") (class "Default")
      (node (ref "U2") (pin "51") (pinfunction "RESERVED_51") (pintype "passive"))
    )
    (net (code "67") (name "unconnected-(U2B-RESERVED-Pad52)") (class "Default")
      (node (ref "U2") (pin "52") (pinfunction "RESERVED_52") (pintype "passive"))
    )
    (net (code "68") (name "unconnected-(U2B-RESERVED-Pad53)") (class "Default")
      (node (ref "U2") (pin "53") (pinfunction "RESERVED_53") (pintype "passive"))
    )
    (net (code "69") (name "unconnected-(U2B-RESERVED-Pad54)") (class "Default")
      (node (ref "U2") (pin "54") (pinfunction "RESERVED_54") (pintype "passive"))
    )
    (net (code "70") (name "unconnected-(U2B-RESERVED-Pad55)") (class "Default")
      (node (ref "U2") (pin "55") (pinfunction "RESERVED_55") (pintype "passive"))
    )
    (net (code "71") (name "unconnected-(U2B-RESERVED-Pad56)") (class "Default")
      (node (ref "U2") (pin "56") (pinfunction "RESERVED_56") (pintype "passive"))
    )
    (net (code "72") (name "unconnected-(U2B-RESERVED-Pad57)") (class "Default")
      (node (ref "U2") (pin "57") (pinfunction "RESERVED_57") (pintype "passive"))
    )
    (net (code "73") (name "unconnected-(U2B-RESERVED-Pad58)") (class "Default")
      (node (ref "U2") (pin "58") (pinfunction "RESERVED_58") (pintype "passive"))
    )
    (net (code "74") (name "unconnected-(U2B-RESERVED-Pad68)") (class "Default")
      (node (ref "U2") (pin "68") (pinfunction "RESERVED_68") (pintype "passive"))
    )
    (net (code "75") (name "unconnected-(U2B-RESERVED-Pad69)") (class "Default")
      (node (ref "U2") (pin "69") (pinfunction "RESERVED_69") (pintype "passive"))
    )
    (net (code "76") (name "unconnected-(U2B-RESERVED-Pad74)") (class "Default")
      (node (ref "U2") (pin "74") (pinfunction "RESERVED_74") (pintype "passive"))
    )
    (net (code "77") (name "unconnected-(U2B-RESERVED-Pad75)") (class "Default")
      (node (ref "U2") (pin "75") (pinfunction "RESERVED_75") (pintype "passive"))
    )
    (net (code "78") (name "unconnected-(U2B-RESERVED-Pad76)") (class "Default")
      (node (ref "U2") (pin "76") (pinfunction "RESERVED_76") (pintype "passive"))
    )
    (net (code "79") (name "unconnected-(U2B-RESERVED-Pad77)") (class "Default")
      (node (ref "U2") (pin "77") (pinfunction "RESERVED_77") (pintype "passive"))
    )
    (net (code "80") (name "unconnected-(U2B-RESERVED-Pad78)") (class "Default")
      (node (ref "U2") (pin "78") (pinfunction "RESERVED_78") (pintype "passive"))
    )
    (net (code "81") (name "unconnected-(U2B-RESERVED-Pad80)") (class "Default")
      (node (ref "U2") (pin "80") (pinfunction "RESERVED_80") (pintype "passive"))
    )
    (net (code "82") (name "unconnected-(U2B-RESERVED-Pad81)") (class "Default")
      (node (ref "U2") (pin "81") (pinfunction "RESERVED_81") (pintype "passive"))
    )
    (net (code "83") (name "unconnected-(U2B-RESERVED-Pad83)") (class "Default")
      (node (ref "U2") (pin "83") (pinfunction "RESERVED_83") (pintype "passive"))
    )
    (net (code "84") (name "unconnected-(U2B-RESERVED-Pad84)") (class "Default")
      (node (ref "U2") (pin "84") (pinfunction "RESERVED_84") (pintype "passive"))
    )
    (net (code "85") (name "unconnected-(U2B-RESERVED-Pad85)") (class "Default")
      (node (ref "U2") (pin "85") (pinfunction "RESERVED_85") (pintype "passive"))
    )
    (net (code "86") (name "unconnected-(U2B-RESERVED-Pad86)") (class "Default")
      (node (ref "U2") (pin "86") (pinfunction "RESERVED_86") (pintype "passive"))
    )
    (net (code "87") (name "unconnected-(U2B-RESERVED-Pad87)") (class "Default")
      (node (ref "U2") (pin "87") (pinfunction "RESERVED_87") (pintype "passive"))
    )
    (net (code "88") (name "unconnected-(U2B-RESERVED-Pad97)") (class "Default")
      (node (ref "U2") (pin "97") (pinfunction "RESERVED_97") (pintype "passive"))
    )
    (net (code "89") (name "unconnected-(U2B-RESERVED-Pad98)") (class "Default")
      (node (ref "U2") (pin "98") (pinfunction "RESERVED_98") (pintype "passive"))
    )
    (net (code "90") (name "unconnected-(U2B-RESERVED-Pad99)") (class "Default")
      (node (ref "U2") (pin "99") (pinfunction "RESERVED_99") (pintype "passive"))
    )
    (net (code "91") (name "unconnected-(U2B-RESERVED-Pad100)") (class "Default")
      (node (ref "U2") (pin "100") (pinfunction "RESERVED_100") (pintype "passive"))
    )
    (net (code "92") (name "unconnected-(U2B-RESERVED-Pad101)") (class "Default")
      (node (ref "U2") (pin "101") (pinfunction "RESERVED_101") (pintype "passive"))
    )
    (net (code "93") (name "unconnected-(U2B-RESERVED-Pad102)") (class "Default")
      (node (ref "U2") (pin "102") (pinfunction "RESERVED_102") (pintype "passive"))
    )
    (net (code "94") (name "unconnected-(U2B-RESERVED-Pad103)") (class "Default")
      (node (ref "U2") (pin "103") (pinfunction "RESERVED_103") (pintype "passive"))
    )
    (net (code "95") (name "unconnected-(U2B-RESERVED-Pad104)") (class "Default")
      (node (ref "U2") (pin "104") (pinfunction "RESERVED_104") (pintype "passive"))
    )
    (net (code "96") (name "unconnected-(U2B-RESERVED-Pad105)") (class "Default")
      (node (ref "U2") (pin "105") (pinfunction "RESERVED_105") (pintype "passive"))
    )
    (net (code "97") (name "unconnected-(U2B-RESERVED-Pad106)") (class "Default")
      (node (ref "U2") (pin "106") (pinfunction "RESERVED_106") (pintype "passive"))
    )
    (net (code "98") (name "unconnected-(U2B-RESERVED-Pad107)") (class "Default")
      (node (ref "U2") (pin "107") (pinfunction "RESERVED_107") (pintype "passive"))
    )
    (net (code "99") (name "unconnected-(U2B-RESERVED-Pad108)") (class "Default")
      (node (ref "U2") (pin "108") (pinfunction "RESERVED_108") (pintype "passive"))
    )
    (net (code "100") (name "unconnected-(U2B-RESERVED-Pad109)") (class "Default")
      (node (ref "U2") (pin "109") (pinfunction "RESERVED_109") (pintype "passive"))
    )
    (net (code "101") (name "unconnected-(USB1-SBU1-Pad9)") (class "Default")
      (node (ref "USB1") (pin "9") (pinfunction "SBU1_9") (pintype "passive"))
    )
    (net (code "102") (name "unconnected-(USB1-SBU2-Pad3)") (class "Default")
      (node (ref "USB1") (pin "3") (pinfunction "SBU2_3") (pintype "passive"))
    )
  )
)
